# Template_PS_2Layer_SCH.net
KiCad netlist of a schematic drawn in Altium Designer
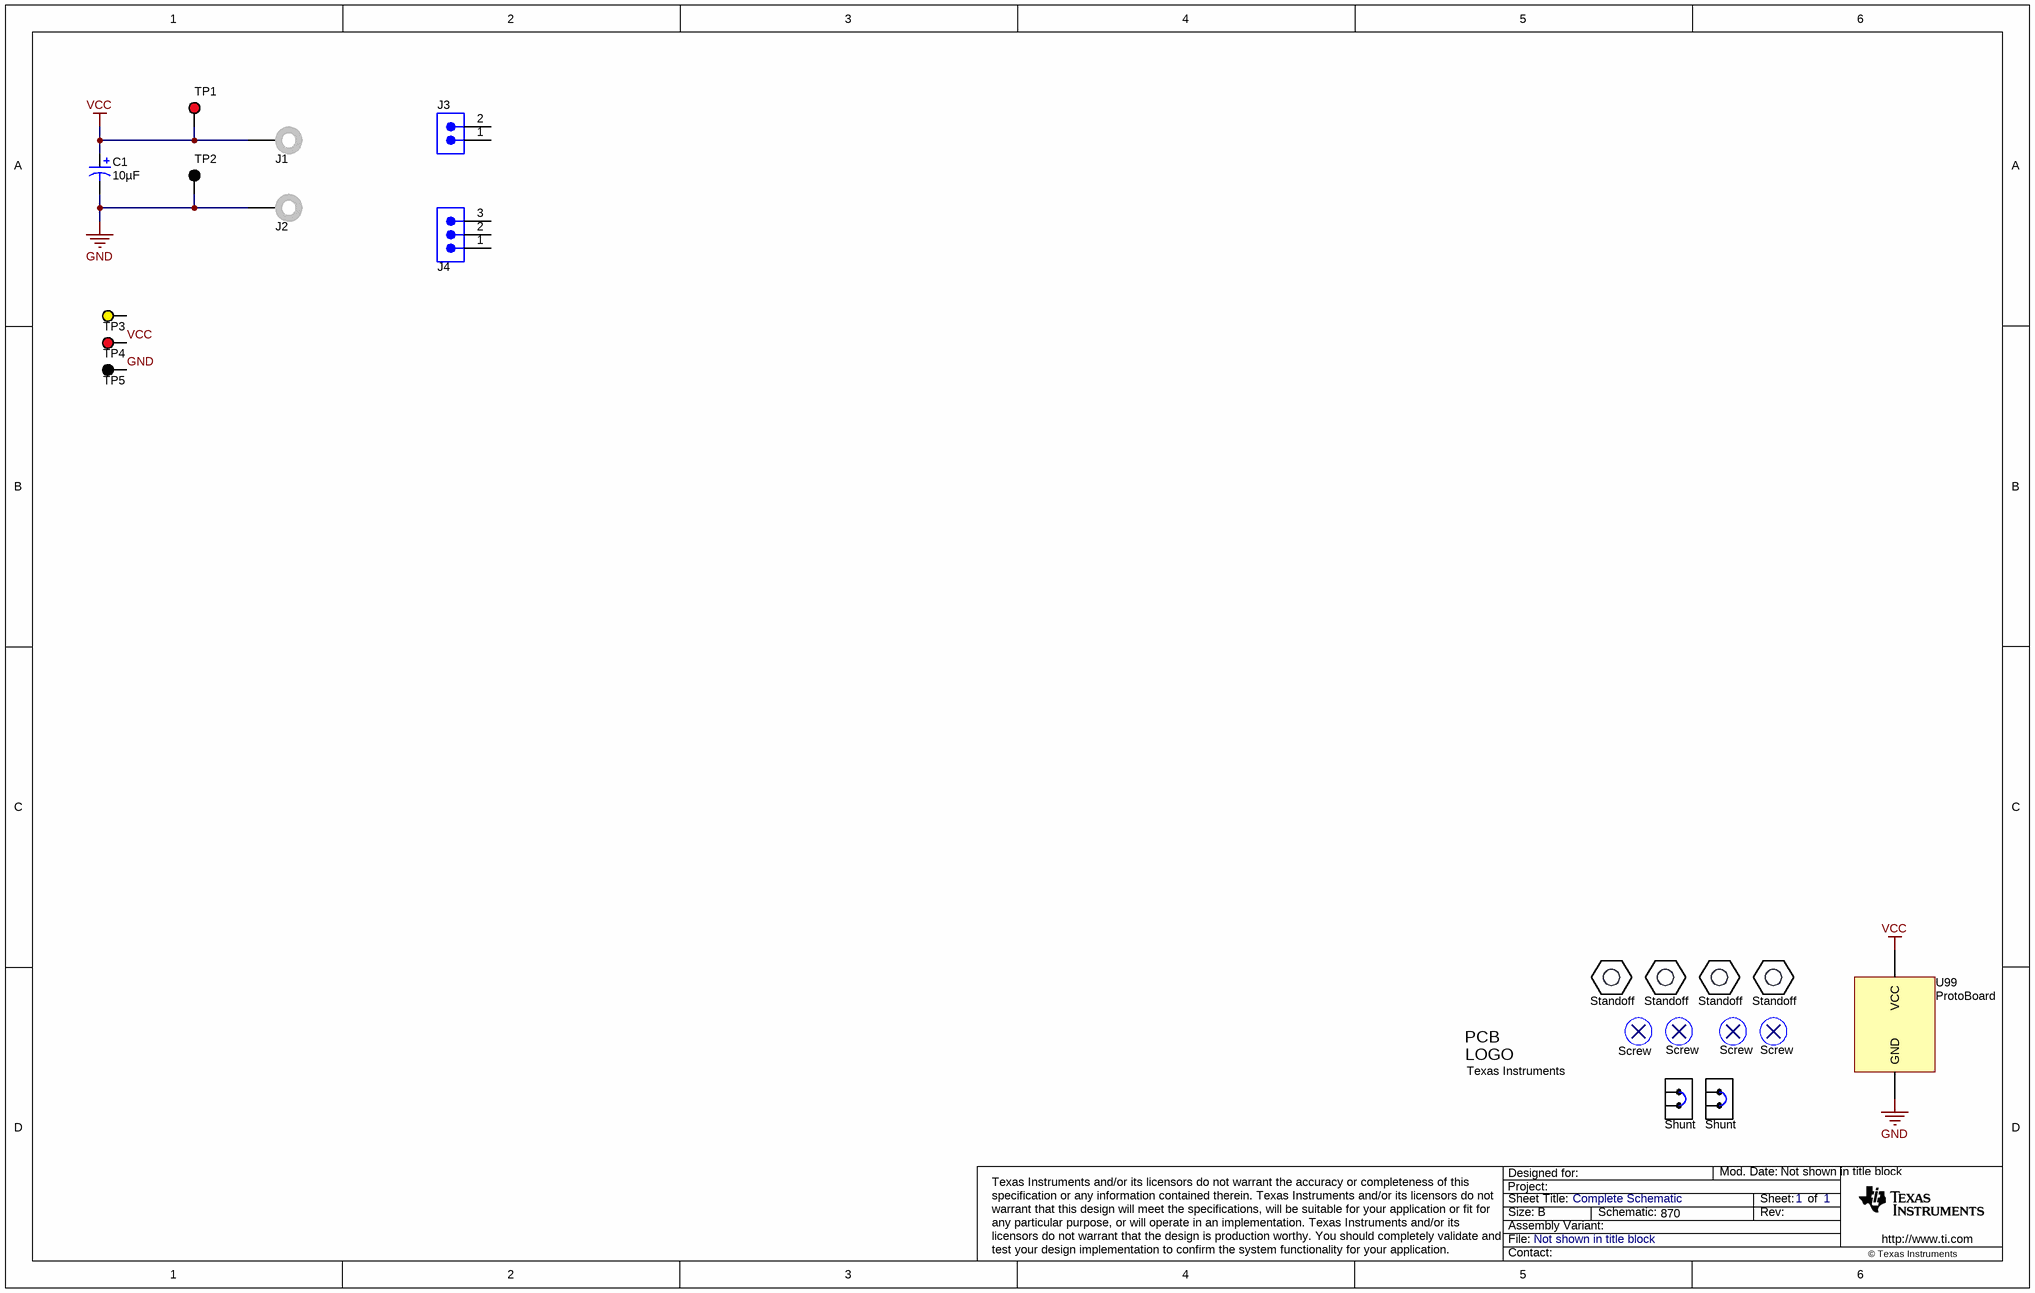
[diagram p0: Template_PS_2Layer_SCH.SchDoc]

(export (version "E")
  (design (tool "Eeschema 10.0.6"))
  (components
    (comp (ref "C1")
      (value "TPSB106M020R1000")
      (footprint "3528-21")
      (description "CAP, TANT, 10uF, 20V, +/-20%, 1 ohm, 3528-21 SMD")
      (fields
        (field (name "MANUFACTURER") "AVX")
        (field (name "VALUEDISPLAYED") "10µF")
        (field (name "PUBLISHER") "Texas Instruments")
      )
      (libsource (lib "TemplateSCHLib") (part "TPSB106M020R1000"))
    )
    (comp (ref "J1")
      (value "Banana Jack, Solder")
      (footprint "JACK NON-INSULATED .218\"")
      (description "JACK NON-INSULATED .218\"")
      (fields
        (field (name "MANUFACTURER") "Keystone")
        (field (name "PARTNUMBER") "575-4")
        (field (name "SYMBOLCREATOR") "Use LDAP id")
      )
      (libsource (lib "TemplateSCHLib") (part "Banana Jack, Solder"))
    )
    (comp (ref "J2")
      (value "Banana Jack, Solder")
      (footprint "JACK NON-INSULATED .218\"")
      (description "JACK NON-INSULATED .218\"")
      (fields
        (field (name "MANUFACTURER") "Keystone")
        (field (name "PARTNUMBER") "575-4")
        (field (name "SYMBOLCREATOR") "Use LDAP id")
      )
      (libsource (lib "TemplateSCHLib") (part "Banana Jack, Solder"))
    )
    (comp (ref "J3")
      (value "961102-6404-AR")
      (footprint "Header 100mil, 1x2")
      (description "CONN HEADER VERT SGL 2POS GOLD")
      (fields
        (field (name "MANUFACTURER") "3M")
        (field (name "ALTERNATE PARTNUMBER") "3M9447-ND")
        (field (name "SYMBOLCREATOR") "Use LDAP id")
      )
      (libsource (lib "MySCHLib") (part "CONN HEADER VERT SGL 2POS GOLD"))
    )
    (comp (ref "J4")
      (value "961103-6404-AR")
      (footprint "CONN HEADER VERT SGL 3POS GOLD")
      (description "CONN HEADER VERT SGL 3POS GOLD")
      (fields (field (name "MANUFACTURER") "3M") (field (name "SYMBOLCREATOR") "Use LDAP id"))
      (libsource (lib "MySCHLib") (part "CONN HEADER VERT SGL 3POS GOLD"))
    )
    (comp (ref "J80")
      (value "Shunt")
      (description "SHUNT LP W/HANDLE 2 POS 30AU")
      (fields
        (field (name "MANUFACTURER") "TE Connectivity")
        (field (name "PARTNUMBER") "881545-2")
        (field (name "SYMBOLCREATOR") "Use LDAP id")
      )
      (libsource (lib "TemplateSCHLib") (part "Shunt, 100mil, Handle"))
    )
    (comp (ref "J81")
      (value "Shunt")
      (description "SHUNT LP W/HANDLE 2 POS 30AU")
      (fields
        (field (name "MANUFACTURER") "TE Connectivity")
        (field (name "PARTNUMBER") "881545-2")
        (field (name "SYMBOLCREATOR") "Use LDAP id")
      )
      (libsource (lib "TemplateSCHLib") (part "Shunt, 100mil, Handle"))
    )
    (comp (ref "Logo1")
      (value "Texas Instruments")
      (footprint "TI_Symbol_Overlay_Small")
      (description "Texas Instrument Corporate Signature")
      (fields (field (name "SYMBOLCREATOR") "codlsc") (field (name "PUBLISHER") "Texas Instruments"))
      (libsource (lib "Logos") (part "TI_Logo"))
    )
    (comp (ref "TP1")
      (value "5005")
      (footprint "Keystone5005")
      (description "Test Point, TH, Compact, Red")
      (fields
        (field (name "MANUFACTURER") "Keystone")
        (field (name "DIGIKEYPARTNUMBER") "5005K-ND")
        (field (name "PUBLISHER") "Texas Instruments")
      )
      (libsource (lib "TemplateSCHLib") (part "5005"))
    )
    (comp (ref "TP2")
      (value "5006")
      (footprint "Keystone5006")
      (description "Test Point, TH, Compact, Black")
      (fields
        (field (name "MANUFACTURER") "Keystone")
        (field (name "DIGIKEYPARTNUMBER") "5006K-ND")
        (field (name "PUBLISHER") "Texas Instruments")
      )
      (libsource (lib "TemplateSCHLib") (part "5006"))
    )
    (comp (ref "TP3")
      (value "5009")
      (footprint "Keystone5009")
      (description "Test Point, TH, Compact, Yellow")
      (fields
        (field (name "MANUFACTURER") "Keystone")
        (field (name "DIGIKEYPARTNUMBER") "5009K-ND")
        (field (name "PUBLISHER") "Texas Instruments")
      )
      (libsource (lib "TemplateSCHLib") (part "5009"))
    )
    (comp (ref "TP4")
      (value "5005")
      (footprint "Keystone5005")
      (description "Test Point, TH, Compact, Red")
      (fields
        (field (name "MANUFACTURER") "Keystone")
        (field (name "DIGIKEYPARTNUMBER") "5005K-ND")
        (field (name "PUBLISHER") "Texas Instruments")
      )
      (libsource (lib "TemplateSCHLib") (part "5005"))
    )
    (comp (ref "TP5")
      (value "5006")
      (footprint "Keystone5006")
      (description "Test Point, TH, Compact, Black")
      (fields
        (field (name "MANUFACTURER") "Keystone")
        (field (name "DIGIKEYPARTNUMBER") "5006K-ND")
        (field (name "PUBLISHER") "Texas Instruments")
      )
      (libsource (lib "TemplateSCHLib") (part "5006"))
    )
    (comp (ref "U90")
      (value "Standoff")
      (footprint "STANDOFF HEX 4-40THR ALUM 1\"L")
      (description "STANDOFF HEX 4-40THR ALUM 1\"L")
      (fields
        (field (name "MANUFACTURER") "Keystone")
        (field (name "PARTNUMBER") "2205")
        (field (name "SYMBOLCREATOR") "Use LDAP id")
      )
      (libsource (lib "TemplateSCHLib") (part "Standoff, 1{dblquote}, 4-40, Alum, F-F"))
    )
    (comp (ref "U91")
      (value "Standoff")
      (footprint "STANDOFF HEX 4-40THR ALUM 1\"L")
      (description "STANDOFF HEX 4-40THR ALUM 1\"L")
      (fields
        (field (name "MANUFACTURER") "Keystone")
        (field (name "PARTNUMBER") "2205")
        (field (name "SYMBOLCREATOR") "Use LDAP id")
      )
      (libsource (lib "TemplateSCHLib") (part "Standoff, 1{dblquote}, 4-40, Alum, F-F"))
    )
    (comp (ref "U92")
      (value "Standoff")
      (footprint "STANDOFF HEX 4-40THR ALUM 1\"L")
      (description "STANDOFF HEX 4-40THR ALUM 1\"L")
      (fields
        (field (name "MANUFACTURER") "Keystone")
        (field (name "PARTNUMBER") "2205")
        (field (name "SYMBOLCREATOR") "Use LDAP id")
      )
      (libsource (lib "TemplateSCHLib") (part "Standoff, 1{dblquote}, 4-40, Alum, F-F"))
    )
    (comp (ref "U93")
      (value "Standoff")
      (footprint "STANDOFF HEX 4-40THR ALUM 1\"L")
      (description "STANDOFF HEX 4-40THR ALUM 1\"L")
      (fields
        (field (name "MANUFACTURER") "Keystone")
        (field (name "PARTNUMBER") "2205")
        (field (name "SYMBOLCREATOR") "Use LDAP id")
      )
      (libsource (lib "TemplateSCHLib") (part "Standoff, 1{dblquote}, 4-40, Alum, F-F"))
    )
    (comp (ref "U94")
      (value "Screw")
      (description "MACHINE SCREW PAN PHILLIPS 4-40")
      (fields
        (field (name "MANUFACTURER") "B&F Fastener Supply")
        (field (name "PARTNUMBER") "PMSSS 440 0025 PH")
        (field (name "SYMBOLCREATOR") "Use LDAP id")
      )
      (libsource (lib "TemplateSCHLib") (part "Machine Screw, 4-40, 0.25{dblquote}"))
    )
    (comp (ref "U95")
      (value "Screw")
      (description "MACHINE SCREW PAN PHILLIPS 4-40")
      (fields
        (field (name "MANUFACTURER") "B&F Fastener Supply")
        (field (name "PARTNUMBER") "PMSSS 440 0025 PH")
        (field (name "SYMBOLCREATOR") "Use LDAP id")
      )
      (libsource (lib "TemplateSCHLib") (part "Machine Screw, 4-40, 0.25{dblquote}"))
    )
    (comp (ref "U96")
      (value "Screw")
      (description "MACHINE SCREW PAN PHILLIPS 4-40")
      (fields
        (field (name "MANUFACTURER") "B&F Fastener Supply")
        (field (name "PARTNUMBER") "PMSSS 440 0025 PH")
        (field (name "SYMBOLCREATOR") "Use LDAP id")
      )
      (libsource (lib "TemplateSCHLib") (part "Machine Screw, 4-40, 0.25{dblquote}"))
    )
    (comp (ref "U97")
      (value "Screw")
      (description "MACHINE SCREW PAN PHILLIPS 4-40")
      (fields
        (field (name "MANUFACTURER") "B&F Fastener Supply")
        (field (name "PARTNUMBER") "PMSSS 440 0025 PH")
        (field (name "SYMBOLCREATOR") "Use LDAP id")
      )
      (libsource (lib "TemplateSCHLib") (part "Machine Screw, 4-40, 0.25{dblquote}"))
    )
    (comp (ref "U99")
      (value "ProtoBoard")
      (footprint "ProtoArea")
      (description "Prototype Area")
      (fields (field (name "MANUFACTURER") "Used in BOM report") (field (name "SYMBOLCREATOR") "Use LDAP id"))
      (libsource (lib "TemplateSCHLib") (part "Proto"))
    )
  )
  (nets
    (net (code "1") (name "GND") (class "Default")
      (node (ref "C1") (pin "2") (pinfunction "-_2") (pintype "passive"))
      (node (ref "J2") (pin "1") (pinfunction "1_1") (pintype "passive"))
      (node (ref "TP2") (pin "1") (pintype "passive"))
      (node (ref "TP5") (pin "1") (pintype "passive"))
      (node (ref "U99") (pin "0") (pinfunction "GND_0") (pintype "passive"))
    )
    (net (code "2") (name "VCC") (class "Default")
      (node (ref "C1") (pin "1") (pinfunction "+_1") (pintype "passive"))
      (node (ref "J1") (pin "1") (pinfunction "1_1") (pintype "passive"))
      (node (ref "TP1") (pin "1") (pintype "passive"))
      (node (ref "TP4") (pin "1") (pintype "passive"))
      (node (ref "U99") (pin "17") (pinfunction "VCC_17") (pintype "passive"))
    )
    (net (code "3") (name "unconnected-(J3-Pad1)") (class "Default")
      (node (ref "J3") (pin "1") (pinfunction "1_1") (pintype "passive"))
    )
    (net (code "4") (name "unconnected-(J3-Pad2)") (class "Default")
      (node (ref "J3") (pin "2") (pinfunction "2_2") (pintype "passive"))
    )
    (net (code "5") (name "unconnected-(J4-Pad1)") (class "Default")
      (node (ref "J4") (pin "1") (pinfunction "1_1") (pintype "passive"))
    )
    (net (code "6") (name "unconnected-(J4-Pad2)") (class "Default")
      (node (ref "J4") (pin "2") (pinfunction "2_2") (pintype "passive"))
    )
    (net (code "7") (name "unconnected-(J4-Pad3)") (class "Default")
      (node (ref "J4") (pin "3") (pinfunction "3_3") (pintype "passive"))
    )
    (net (code "8") (name "unconnected-(TP3-Pad1)") (class "Default")
      (node (ref "TP3") (pin "1") (pintype "passive"))
    )
  )
)
